# Power_Sheet.net
KiCad netlist of a schematic drawn in Altium Designer
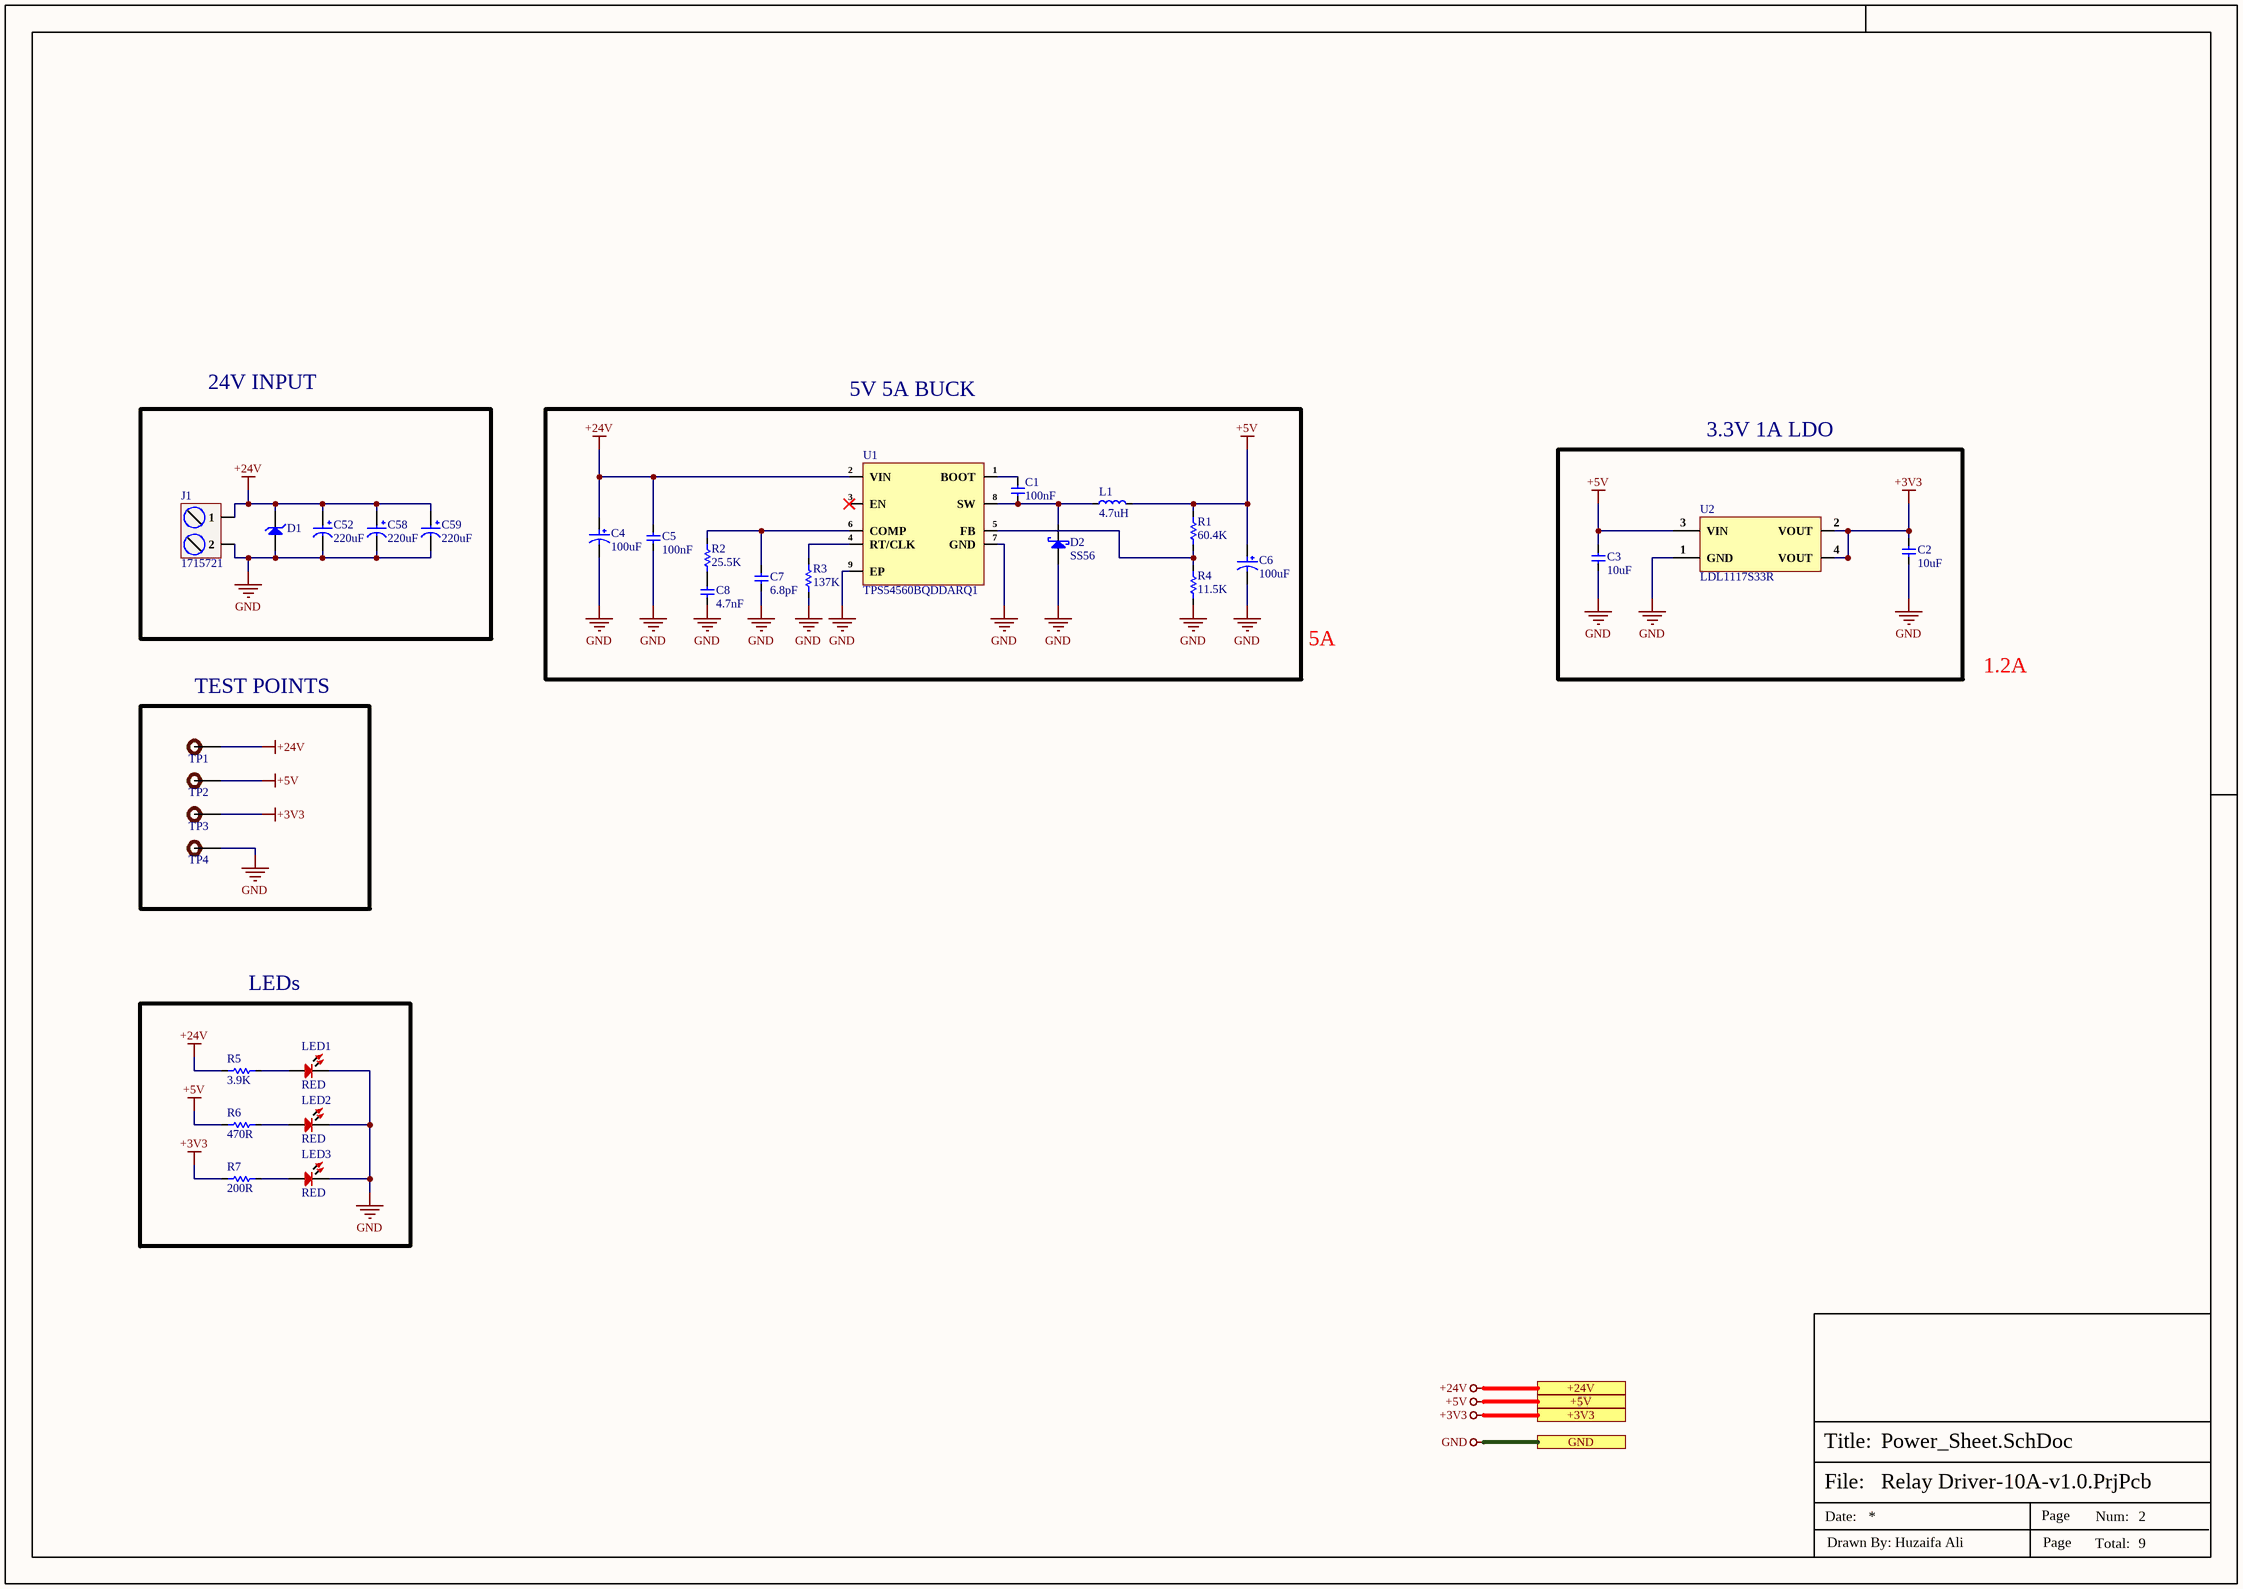
[diagram p0: Power_Sheet.SchDoc]

(export (version "E")
  (design (tool "Eeschema 10.0.6"))
  (components
    (comp (ref "C1")
      (value "100nF")
      (footprint "cap-0402")
      (description "CAP CER 0.1UF 50V X7R 0402")
      (fields
        (field (name "MANUFACTURER") "TDK")
        (field (name "MANUFACTURER PART NUMBER") "C1005X7R1H104KT000F")
      )
      (libsource (lib "eSpark Libraries") (part "C1005X7R1H104KT000F"))
    )
    (comp (ref "C2")
      (value "10uF")
      (footprint "Cap-0603")
      (description "CAP CER 10UF 25V X5R 0603")
      (fields
        (field (name "MANUFACTURER") "TDK")
        (field (name "MANUFACTURER PART NUMBER") "C1608X5R1E106M080AC")
      )
      (libsource (lib "eSpark Libraries") (part "C1608X5R1E106M080AC"))
    )
    (comp (ref "C3")
      (value "10uF")
      (footprint "Cap-0603")
      (description "CAP CER 10UF 25V X5R 0603")
      (fields
        (field (name "MANUFACTURER") "TDK")
        (field (name "MANUFACTURER PART NUMBER") "C1608X5R1E106M080AC")
      )
      (libsource (lib "eSpark Libraries") (part "C1608X5R1E106M080AC"))
    )
    (comp (ref "C4")
      (value "100uF")
      (footprint "RVT1A101M0605")
      (description "100uF 10V 55mA@120Hz ±20% SMD,D6.3xL5.4mm Aluminum Electrolytic Capacitors - SMD ROHS")
      (fields
        (field (name "MANUFACTURER") "ROQANG")
        (field (name "MANUFACTURER PART NUMBER") "RVT1A101M0605")
      )
      (libsource (lib "eSpark Libraries") (part "RVT1A101M0605"))
    )
    (comp (ref "C5")
      (value "100nF")
      (footprint "cap-0402")
      (description "CAP CER 0.1UF 50V X7R 0402")
      (fields
        (field (name "MANUFACTURER") "TDK")
        (field (name "MANUFACTURER PART NUMBER") "C1005X7R1H104KT000F")
      )
      (libsource (lib "eSpark Libraries") (part "C1005X7R1H104KT000F"))
    )
    (comp (ref "C6")
      (value "100uF")
      (footprint "RVT1A101M0605")
      (description "100uF 10V 55mA@120Hz ±20% SMD,D6.3xL5.4mm Aluminum Electrolytic Capacitors - SMD ROHS")
      (fields
        (field (name "MANUFACTURER") "ROQANG")
        (field (name "MANUFACTURER PART NUMBER") "RVT1A101M0605")
      )
      (libsource (lib "eSpark Libraries") (part "RVT1A101M0605"))
    )
    (comp (ref "C7")
      (value "6.8pF")
      (footprint "Cap-0402")
      (description "CAP CER 6.8PF 50V C0G/NPO 0402")
      (fields
        (field (name "MANUFACTURER") "Yageo")
        (field (name "MANUFACTURER PART NUMBER") "CC0402CRNPO9BN6R8")
      )
      (libsource (lib "eSpark Libraries") (part "CC0402CRNPO9BN6R8"))
    )
    (comp (ref "C8")
      (value "4.7nF")
      (footprint "Cap-0402")
      (description "CAP CER 4700PF 50V X7R 0402")
      (fields
        (field (name "MANUFACTURER") "Yageo")
        (field (name "MANUFACTURER PART NUMBER") "CC0402KRX7R9BB472")
      )
      (libsource (lib "eSpark Libraries") (part "CC0402KRX7R9BB472"))
    )
    (comp (ref "C52")
      (value "220uF")
      (footprint "UCD-220uF-10mmDia")
      (description "CAP ALUM 220UF 20% 50V SMD")
      (fields
        (field (name "MANUFACTURER") "Nichicon")
        (field (name "MANUFACTURER PART NUMBER") "UCD1H221MNL1GS")
      )
      (libsource (lib "eSpark Libraries") (part "UCD1H221MNL1GS"))
    )
    (comp (ref "C58")
      (value "220uF")
      (footprint "UCD-220uF-10mmDia")
      (description "CAP ALUM 220UF 20% 50V SMD")
      (fields
        (field (name "MANUFACTURER") "Nichicon")
        (field (name "MANUFACTURER PART NUMBER") "UCD1H221MNL1GS")
      )
      (libsource (lib "eSpark Libraries") (part "UCD1H221MNL1GS"))
    )
    (comp (ref "C59")
      (value "220uF")
      (footprint "UCD-220uF-10mmDia")
      (description "CAP ALUM 220UF 20% 50V SMD")
      (fields
        (field (name "MANUFACTURER") "Nichicon")
        (field (name "MANUFACTURER PART NUMBER") "UCD1H221MNL1GS")
      )
      (libsource (lib "eSpark Libraries") (part "UCD1H221MNL1GS"))
    )
    (comp (ref "D1")
      (value "SMBJ28A-13-F")
      (footprint "SMB_")
      (description "TVS DIODE 28VWM 45.4VC SMB")
      (fields (field (name "MANUFACTURER") "Diodes"))
      (libsource (lib "eSpark Libraries") (part "SMBJ28A-13-F"))
    )
    (comp (ref "D2")
      (value "SS56")
      (footprint "SMA")
      (description "DIODE SCHOTTKY 60V 5A SMA")
      (fields (field (name "MANUFACTURER") "MDD"))
      (libsource (lib "eSpark Libraries") (part "SS56"))
    )
    (comp (ref "J1")
      (value "1715721")
      (footprint "1715721")
      (description "TERM BLK 2P SIDE ENT 5.08MM PCB")
      (fields (field (name "MANUFACTURER") "Phoenix Contact"))
      (libsource (lib "eSpark Libraries") (part "1715721"))
    )
    (comp (ref "L1")
      (value "4.7uH")
      (footprint "YSPI1050-4R7M")
      (description "8A 4.7uH ±20% SMD,10x10.1mm Power Inductors ROHS")
      (fields
        (field (name "MANUFACTURER") "YJYCOIN")
        (field (name "MANUFACTURER PART NUMBER") "YSPI1050-4R7M")
      )
      (libsource (lib "eSpark Libraries") (part "YSPI1050-4R7M"))
    )
    (comp (ref "LED1")
      (value "RED")
      (footprint "LED-0603")
      (description "RED LED 0603 Light Emitting Diodes")
      (fields
        (field (name "MANUFACTURER") "Foshan NationStar Optoelectronics")
        (field (name "MANUFACTURER PART NUMBER") "NCD0603R3")
      )
      (libsource (lib "eSpark Libraries") (part "NCD0603R3"))
    )
    (comp (ref "LED2")
      (value "RED")
      (footprint "LED-0603")
      (description "RED LED 0603 Light Emitting Diodes")
      (fields
        (field (name "MANUFACTURER") "Foshan NationStar Optoelectronics")
        (field (name "MANUFACTURER PART NUMBER") "NCD0603R3")
      )
      (libsource (lib "eSpark Libraries") (part "NCD0603R3"))
    )
    (comp (ref "LED3")
      (value "RED")
      (footprint "LED-0603")
      (description "RED LED 0603 Light Emitting Diodes")
      (fields
        (field (name "MANUFACTURER") "Foshan NationStar Optoelectronics")
        (field (name "MANUFACTURER PART NUMBER") "NCD0603R3")
      )
      (libsource (lib "eSpark Libraries") (part "NCD0603R3"))
    )
    (comp (ref "R1")
      (value "60.4K")
      (footprint "Res-0402")
      (description "60.4kΩ 50V 62.5mW Thick Film Resistors ±1% 0402 Chip Resistor - Surface Mount ROHS")
      (fields (field (name "MANUFACTURER") "VO") (field (name "MANUFACTURER PART NUMBER") "SCR0402F60K4"))
      (libsource (lib "eSpark Libraries") (part "SCR0402F60K4"))
    )
    (comp (ref "R2")
      (value "25.5K")
      (footprint "Res-0402")
      (description "62.5mW Thick Film Resistors 50V ±100ppm/℃ ±1% 25.5kΩ 0402 Chip Resistor - Surface Mount ROHS")
      (fields
        (field (name "LCSC PART NUMBER") "C26970")
        (field (name "MANUFACTURER") "Royal Electronic Factory")
      )
      (libsource (lib "eSpark Libraries") (part "0402WGF2552TCE"))
    )
    (comp (ref "R3")
      (value "137K")
      (footprint "Res-0402")
      (description "RES SMD 137K OHM 0.1% 1/16W 0402")
      (fields (field (name "LCSC PART NUMBER") "C852519") (field (name "MANUFACTURER") "Yageo"))
      (libsource (lib "eSpark Libraries") (part "RT0402BRD07137KL"))
    )
    (comp (ref "R4")
      (value "11.5K")
      (footprint "Res-0402")
      (description "11.5kΩ 50V 62.5mW Thick Film Resistors ±100ppm/℃ ±1%  0402 Chip Resistor - Surface Mount ROHS")
      (fields
        (field (name "MANUFACTURER") "FOJAN")
        (field (name "MANUFACTURER PART NUMBER") "FRC0402F1152TS")
      )
      (libsource (lib "eSpark Libraries") (part "FRC0402F1152TS"))
    )
    (comp (ref "R5")
      (value "3.9K")
      (footprint "Res-0402")
      (description "RES 3.9K OHM 1% 1/16W 0402")
      (fields
        (field (name "MANUFACTURER") "Yageo")
        (field (name "MANUFACTURER PART NUMBER") "RC0402FR-073K9L")
      )
      (libsource (lib "eSpark Libraries") (part "RC0402FR-073K9L"))
    )
    (comp (ref "R6")
      (value "470R")
      (footprint "Res-0402")
      (description "RES 470 OHM 1% 1/16W 0402")
      (fields
        (field (name "MANUFACTURER") "Yageo")
        (field (name "MANUFACTURER PART NUMBER") "RC0402FR-07470RL")
      )
      (libsource (lib "eSpark Libraries") (part "RC0402FR-07470RL"))
    )
    (comp (ref "R7")
      (value "200R")
      (footprint "Res-0402")
      (description "RES 200 OHM 1% 1/16W 0402")
      (fields
        (field (name "MANUFACTURER") "Yageo")
        (field (name "MANUFACTURER PART NUMBER") "RC0402FR-07200RL")
      )
      (libsource (lib "eSpark Libraries") (part "RC0402FR-07200RL"))
    )
    (comp (ref "TP1")
      (value "TEST POINT")
      (footprint "Test-point")
      (description "Test Point ON")
      (libsource (lib "eSpark Libraries") (part "TEST POINT"))
    )
    (comp (ref "TP2")
      (value "TEST POINT")
      (footprint "Test-point")
      (description "Test Point ON")
      (libsource (lib "eSpark Libraries") (part "TEST POINT"))
    )
    (comp (ref "TP3")
      (value "TEST POINT")
      (footprint "Test-point")
      (description "Test Point ON")
      (libsource (lib "eSpark Libraries") (part "TEST POINT"))
    )
    (comp (ref "TP4")
      (value "TEST POINT")
      (footprint "Test-point")
      (description "Test Point ON")
      (libsource (lib "eSpark Libraries") (part "TEST POINT"))
    )
    (comp (ref "U1")
      (value "TPS54560BQDDARQ1")
      (footprint "8-SO PowerPad")
      (description "IC REG BCK SPLIT RAIL ADJ 8SOPWR")
      (fields (field (name "MANUFACTURER") "Texas Instruments") (field (name "LCSC PART NUMBER") "C2072188"))
      (libsource (lib "eSpark Libraries") (part "TPS54560BQDDARQ1"))
    )
    (comp (ref "U2")
      (value "LDL1117S33R")
      (footprint "SOT- 223")
      (description "IC REG LINEAR 3.3V 1.2A SOT223")
      (fields (field (name "MANUFACTURER") "STMicroelectronics") (field (name "LCSC PART NUMBER") "C435835"))
      (libsource (lib "eSpark Libraries") (part "LDL1117S33R"))
    )
  )
  (nets
    (net (code "1") (name "+3V3") (class "Default")
      (node (ref "C2") (pin "2") (pinfunction "2_2") (pintype "passive"))
      (node (ref "R7") (pin "1") (pinfunction "1_1") (pintype "passive"))
      (node (ref "TP3") (pin "1") (pinfunction "1_1") (pintype "passive"))
      (node (ref "U2") (pin "2") (pinfunction "VOUT_2") (pintype "passive"))
      (node (ref "U2") (pin "4") (pinfunction "VOUT_4") (pintype "passive"))
    )
    (net (code "2") (name "+5V") (class "Default")
      (node (ref "C3") (pin "2") (pinfunction "2_2") (pintype "passive"))
      (node (ref "C6") (pin "1") (pintype "passive"))
      (node (ref "L1") (pin "2") (pinfunction "2_2") (pintype "passive"))
      (node (ref "R1") (pin "2") (pinfunction "2_2") (pintype "passive"))
      (node (ref "R6") (pin "1") (pinfunction "1_1") (pintype "passive"))
      (node (ref "TP2") (pin "1") (pinfunction "1_1") (pintype "passive"))
      (node (ref "U2") (pin "3") (pinfunction "VIN_3") (pintype "passive"))
    )
    (net (code "3") (name "+24V") (class "Default")
      (node (ref "C4") (pin "1") (pintype "passive"))
      (node (ref "C5") (pin "2") (pinfunction "2_2") (pintype "passive"))
      (node (ref "C52") (pin "1") (pinfunction "1_1") (pintype "passive"))
      (node (ref "C58") (pin "1") (pinfunction "1_1") (pintype "passive"))
      (node (ref "C59") (pin "1") (pinfunction "1_1") (pintype "passive"))
      (node (ref "D1") (pin "2") (pinfunction "K_2") (pintype "passive"))
      (node (ref "J1") (pin "1") (pinfunction "1_1") (pintype "passive"))
      (node (ref "R5") (pin "1") (pinfunction "1_1") (pintype "passive"))
      (node (ref "TP1") (pin "1") (pinfunction "1_1") (pintype "passive"))
      (node (ref "U1") (pin "2") (pinfunction "VIN_2") (pintype "passive"))
    )
    (net (code "4") (name "GND") (class "Default")
      (node (ref "C2") (pin "1") (pinfunction "1_1") (pintype "passive"))
      (node (ref "C3") (pin "1") (pinfunction "1_1") (pintype "passive"))
      (node (ref "C4") (pin "2") (pintype "passive"))
      (node (ref "C5") (pin "1") (pinfunction "1_1") (pintype "passive"))
      (node (ref "C52") (pin "2") (pinfunction "2_2") (pintype "passive"))
      (node (ref "C58") (pin "2") (pinfunction "2_2") (pintype "passive"))
      (node (ref "C59") (pin "2") (pinfunction "2_2") (pintype "passive"))
      (node (ref "C6") (pin "2") (pintype "passive"))
      (node (ref "C7") (pin "1") (pinfunction "1_1") (pintype "passive"))
      (node (ref "C8") (pin "1") (pinfunction "1_1") (pintype "passive"))
      (node (ref "D1") (pin "1") (pinfunction "A_1") (pintype "passive"))
      (node (ref "D2") (pin "2") (pinfunction "A_2") (pintype "passive"))
      (node (ref "J1") (pin "2") (pinfunction "2_2") (pintype "passive"))
      (node (ref "LED1") (pin "2") (pinfunction "2_2") (pintype "passive"))
      (node (ref "LED2") (pin "2") (pinfunction "2_2") (pintype "passive"))
      (node (ref "LED3") (pin "2") (pinfunction "2_2") (pintype "passive"))
      (node (ref "R3") (pin "1") (pinfunction "1_1") (pintype "passive"))
      (node (ref "R4") (pin "1") (pinfunction "1_1") (pintype "passive"))
      (node (ref "TP4") (pin "1") (pinfunction "1_1") (pintype "passive"))
      (node (ref "U1") (pin "7") (pinfunction "GND_7") (pintype "passive"))
      (node (ref "U1") (pin "9") (pinfunction "EP_9") (pintype "passive"))
      (node (ref "U2") (pin "1") (pinfunction "GND_1") (pintype "passive"))
    )
    (net (code "5") (name "Net-(C8-Pad2)") (class "Default")
      (node (ref "C8") (pin "2") (pinfunction "2_2") (pintype "passive"))
      (node (ref "R2") (pin "1") (pinfunction "1_1") (pintype "passive"))
    )
    (net (code "6") (name "Net-(D2-K)") (class "Default")
      (node (ref "C1") (pin "1") (pinfunction "1_1") (pintype "passive"))
      (node (ref "D2") (pin "1") (pinfunction "K_1") (pintype "passive"))
      (node (ref "L1") (pin "1") (pinfunction "1_1") (pintype "passive"))
      (node (ref "U1") (pin "8") (pinfunction "SW_8") (pintype "passive"))
    )
    (net (code "7") (name "Net-(LED1-Pad1)") (class "Default")
      (node (ref "LED1") (pin "1") (pinfunction "1_1") (pintype "passive"))
      (node (ref "R5") (pin "2") (pinfunction "2_2") (pintype "passive"))
    )
    (net (code "8") (name "Net-(LED2-Pad1)") (class "Default")
      (node (ref "LED2") (pin "1") (pinfunction "1_1") (pintype "passive"))
      (node (ref "R6") (pin "2") (pinfunction "2_2") (pintype "passive"))
    )
    (net (code "9") (name "Net-(LED3-Pad1)") (class "Default")
      (node (ref "LED3") (pin "1") (pinfunction "1_1") (pintype "passive"))
      (node (ref "R7") (pin "2") (pinfunction "2_2") (pintype "passive"))
    )
    (net (code "10") (name "Net-(U1-BOOT)") (class "Default")
      (node (ref "C1") (pin "2") (pinfunction "2_2") (pintype "passive"))
      (node (ref "U1") (pin "1") (pinfunction "BOOT_1") (pintype "passive"))
    )
    (net (code "11") (name "Net-(U1-COMP)") (class "Default")
      (node (ref "C7") (pin "2") (pinfunction "2_2") (pintype "passive"))
      (node (ref "R2") (pin "2") (pinfunction "2_2") (pintype "passive"))
      (node (ref "U1") (pin "6") (pinfunction "COMP_6") (pintype "passive"))
    )
    (net (code "12") (name "Net-(U1-FB)") (class "Default")
      (node (ref "R1") (pin "1") (pinfunction "1_1") (pintype "passive"))
      (node (ref "R4") (pin "2") (pinfunction "2_2") (pintype "passive"))
      (node (ref "U1") (pin "5") (pinfunction "FB_5") (pintype "passive"))
    )
    (net (code "13") (name "Net-(U1-RT{slash}CLK)") (class "Default")
      (node (ref "R3") (pin "2") (pinfunction "2_2") (pintype "passive"))
      (node (ref "U1") (pin "4") (pinfunction "RT/CLK_4") (pintype "passive"))
    )
    (net (code "14") (name "unconnected-(U1-EN-Pad3)") (class "Default")
      (node (ref "U1") (pin "3") (pinfunction "EN_3") (pintype "passive+no_connect"))
    )
  )
)
